# MCU_Core.net
KiCad netlist of a schematic drawn in Altium Designer
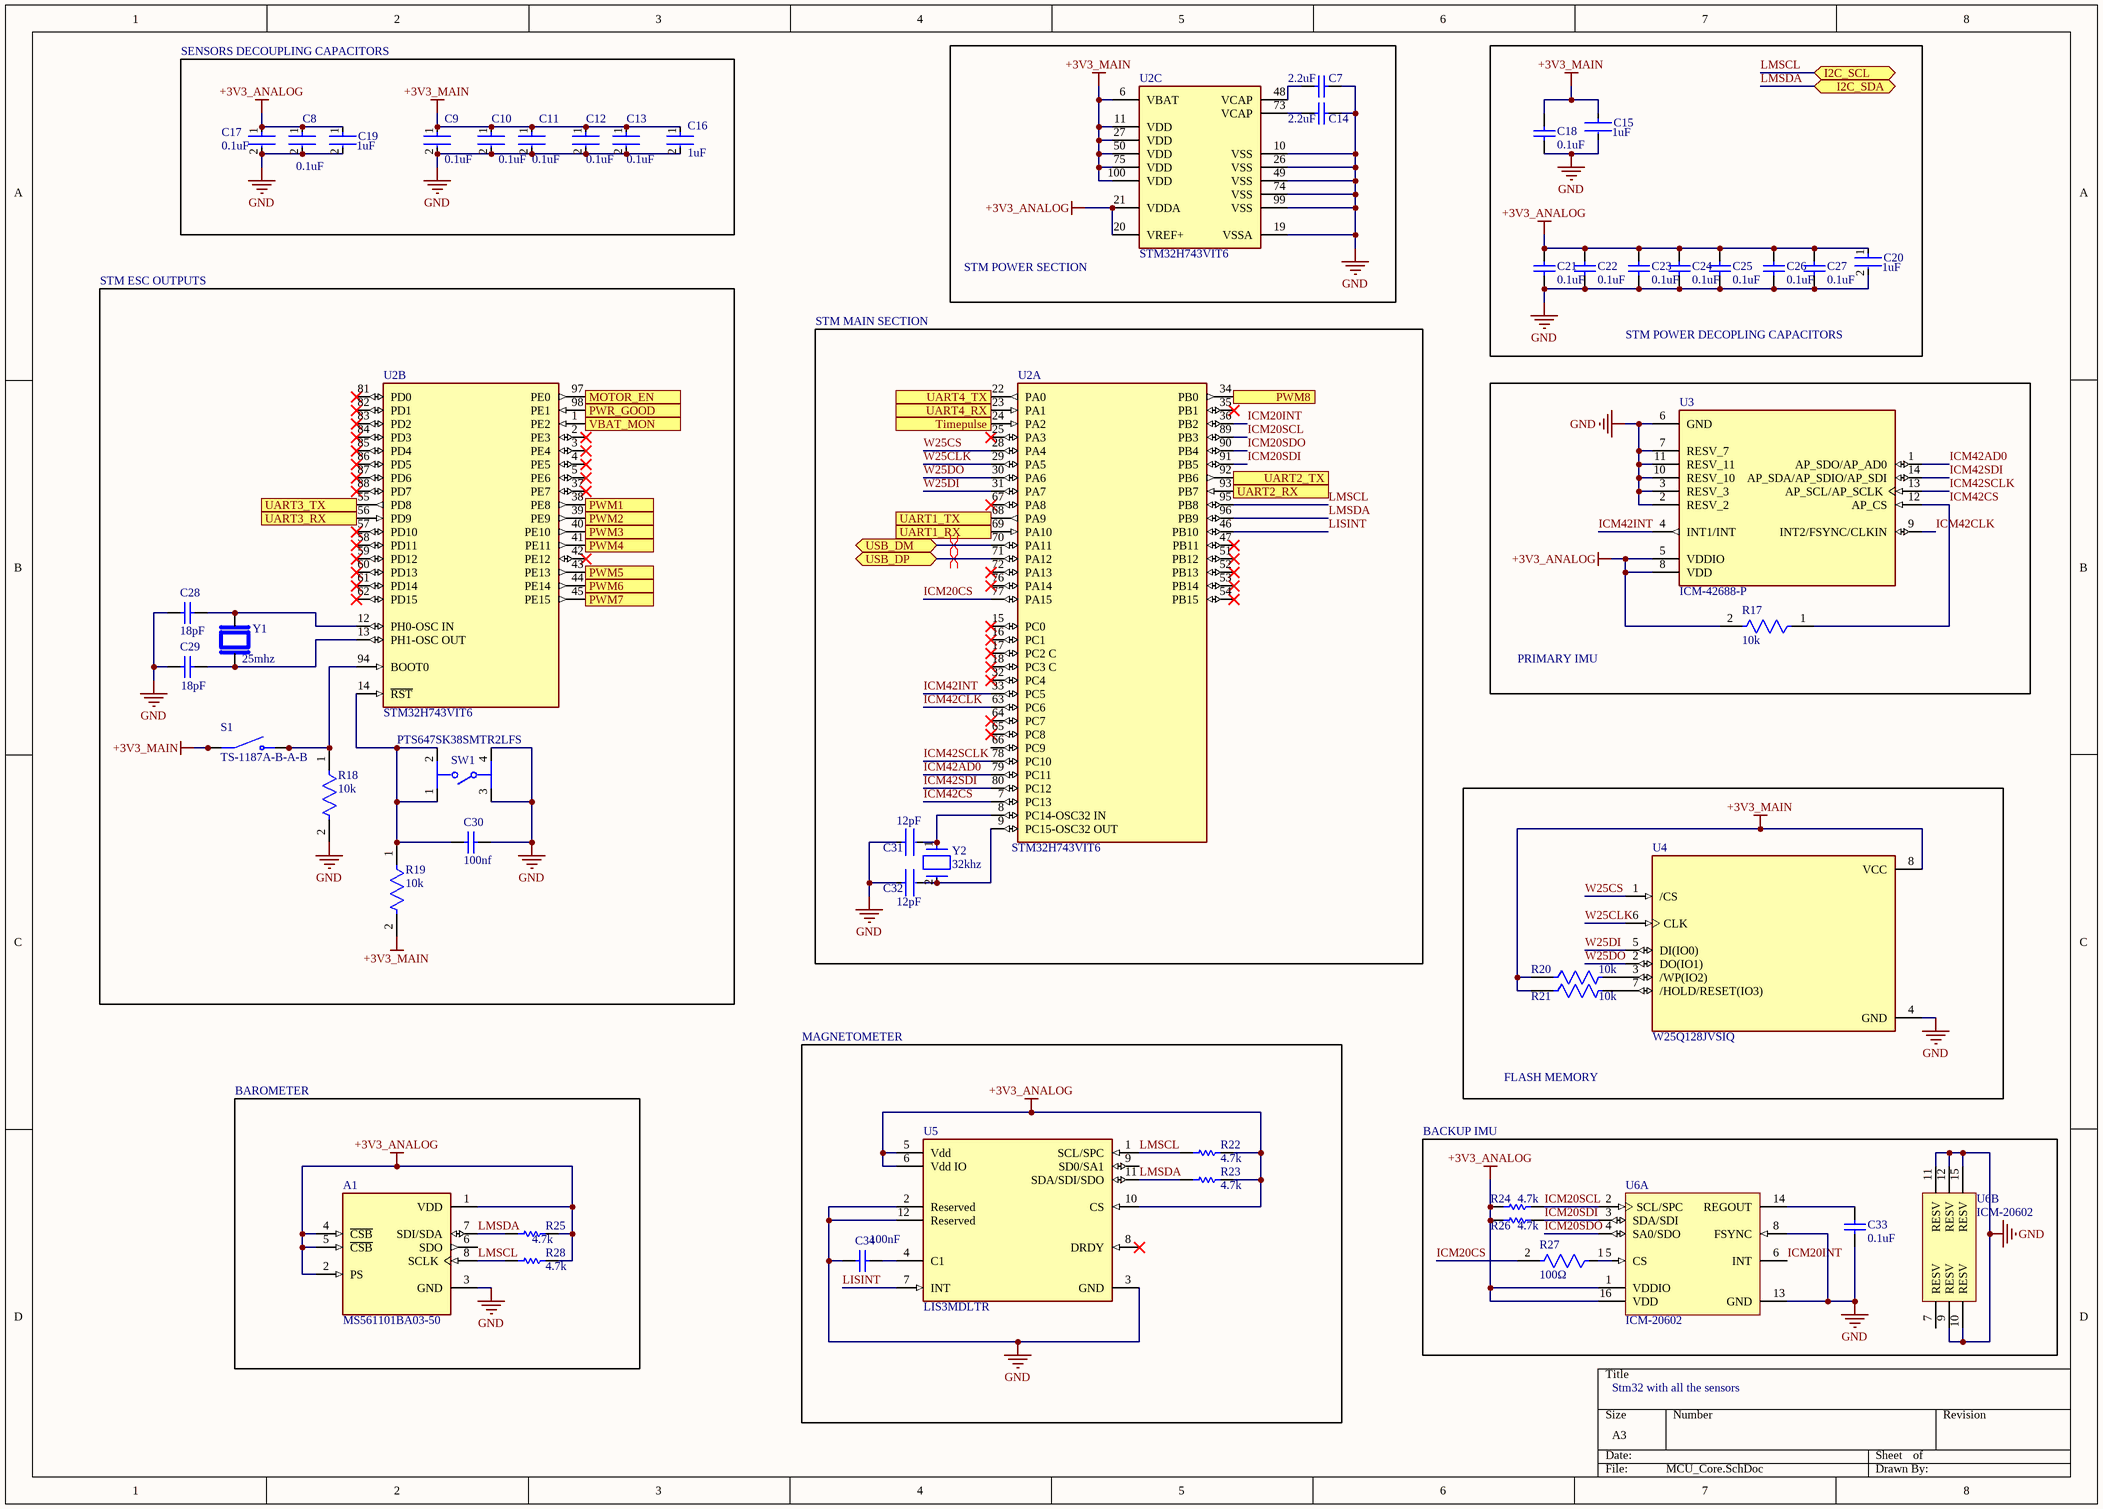
[diagram p0: MCU_Core.SchDoc]

(export (version "E")
  (design (tool "Eeschema 10.0.6"))
  (components
    (comp (ref "A1")
      (value "MS561101BA03-50")
      (footprint "XDCR_MS561101BA03-50")
      (description "Sensor;MS5611-BT M-CAPS 3X5X1MM T&R;Pressure;MS561101BA03-50 ¦ TE Connectivity MS561101BA03-50")
      (fields (field (name "MF") "TE Connectivity"))
      (libsource (lib "MS561101BA03-50") (part "MS561101BA03-50"))
    )
    (comp (ref "C7")
      (value "2.2uF")
      (footprint "CAPC1608X90X35ML15T15")
      (fields
        (field (name "PART NUMBER") "06031A2R2CAT2A")
        (field (name "MANUFACTURER") "AVX Interconnect / Elco")
      )
      (libsource (lib "Altium Content Vault") (part "CAP"))
    )
    (comp (ref "C8")
      (value "0.1uF")
      (footprint "FP-0201-L_0_6_0_05-W_0_3-MFG")
      (description "None")
      (fields (field (name "TOLERANCE") "10%"))
      (libsource (lib "Altium Content Vault") (part "b4654b650e69147ec39a6b967a45e02"))
    )
    (comp (ref "C9")
      (value "0.1uF")
      (footprint "FP-0201-L_0_6_0_05-W_0_3-MFG")
      (description "None")
      (fields (field (name "TOLERANCE") "10%"))
      (libsource (lib "Altium Content Vault") (part "b4654b650e69147ec39a6b967a45e02"))
    )
    (comp (ref "C10")
      (value "0.1uF")
      (footprint "FP-0201-L_0_6_0_05-W_0_3-MFG")
      (description "None")
      (fields (field (name "TOLERANCE") "10%"))
      (libsource (lib "Altium Content Vault") (part "b4654b650e69147ec39a6b967a45e02"))
    )
    (comp (ref "C11")
      (value "0.1uF")
      (footprint "FP-0201-L_0_6_0_05-W_0_3-MFG")
      (description "None")
      (fields (field (name "TOLERANCE") "10%"))
      (libsource (lib "Altium Content Vault") (part "b4654b650e69147ec39a6b967a45e02"))
    )
    (comp (ref "C12")
      (value "0.1uF")
      (footprint "FP-0201-L_0_6_0_05-W_0_3-MFG")
      (description "None")
      (fields (field (name "TOLERANCE") "10%"))
      (libsource (lib "Altium Content Vault") (part "b4654b650e69147ec39a6b967a45e02"))
    )
    (comp (ref "C13")
      (value "0.1uF")
      (footprint "FP-0201-L_0_6_0_05-W_0_3-MFG")
      (description "None")
      (fields (field (name "TOLERANCE") "10%"))
      (libsource (lib "Altium Content Vault") (part "b4654b650e69147ec39a6b967a45e02"))
    )
    (comp (ref "C14")
      (value "2.2uF")
      (footprint "CAPC1608X90X35ML15T15")
      (fields
        (field (name "PART NUMBER") "06031A2R2CAT2A")
        (field (name "MANUFACTURER") "AVX Interconnect / Elco")
      )
      (libsource (lib "Altium Content Vault") (part "CAP"))
    )
    (comp (ref "C15")
      (value "1uF")
      (footprint "FP-GCJ21B-0_3-IPC_B")
      (description "Multilayer Ceramic Capacitors MLCC - SMD/SMT 0805 1uF 10%, 16VDC,  X8L +15/-40%")
      (libsource (lib "") (part "02cd4be3c70576c341d710602a673aa_1"))
    )
    (comp (ref "C16")
      (value "1uF")
      (footprint "FP-GCJ21B-0_3-IPC_B")
      (description "Multilayer Ceramic Capacitors MLCC - SMD/SMT 0805 1uF 10%, 16VDC,  X8L +15/-40%")
      (libsource (lib "Altium Content Vault") (part "02cd4be3c70576c341d710602a673aa"))
    )
    (comp (ref "C17")
      (value "0.1uF")
      (footprint "FP-0201-L_0_6_0_05-W_0_3-MFG")
      (description "None")
      (fields (field (name "TOLERANCE") "10%"))
      (libsource (lib "Altium Content Vault") (part "b4654b650e69147ec39a6b967a45e02"))
    )
    (comp (ref "C18")
      (value "0.1uF")
      (footprint "CAPC1608X87X35ML15T15")
      (fields (field (name "PART NUMBER") "C0603T104K3RCLTU") (field (name "MANUFACTURER") "Kemet"))
      (libsource (lib "Altium Content Vault") (part "CAP"))
    )
    (comp (ref "C19")
      (value "1uF")
      (footprint "FP-GCJ21B-0_3-IPC_B")
      (description "Multilayer Ceramic Capacitors MLCC - SMD/SMT 0805 1uF 10%, 16VDC,  X8L +15/-40%")
      (libsource (lib "Altium Content Vault") (part "02cd4be3c70576c341d710602a673aa"))
    )
    (comp (ref "C20")
      (value "1uF")
      (footprint "FP-GCJ21B-0_3-IPC_B")
      (description "Multilayer Ceramic Capacitors MLCC - SMD/SMT 0805 1uF 10%, 16VDC,  X8L +15/-40%")
      (libsource (lib "Altium Content Vault") (part "02cd4be3c70576c341d710602a673aa"))
    )
    (comp (ref "C21")
      (value "0.1uF")
      (footprint "CAPC1608X87X35ML15T15")
      (fields (field (name "PART NUMBER") "C0603T104K3RCLTU") (field (name "MANUFACTURER") "Kemet"))
      (libsource (lib "Altium Content Vault") (part "CAP"))
    )
    (comp (ref "C22")
      (value "0.1uF")
      (footprint "CAPC1608X87X35ML15T15")
      (fields (field (name "PART NUMBER") "C0603T104K3RCLTU") (field (name "MANUFACTURER") "Kemet"))
      (libsource (lib "Altium Content Vault") (part "CAP"))
    )
    (comp (ref "C23")
      (value "0.1uF")
      (footprint "CAPC1608X87X35ML15T15")
      (fields (field (name "PART NUMBER") "C0603T104K3RCLTU") (field (name "MANUFACTURER") "Kemet"))
      (libsource (lib "Altium Content Vault") (part "CAP"))
    )
    (comp (ref "C24")
      (value "0.1uF")
      (footprint "CAPC1608X87X35ML15T15")
      (fields (field (name "PART NUMBER") "C0603T104K3RCLTU") (field (name "MANUFACTURER") "Kemet"))
      (libsource (lib "Altium Content Vault") (part "CAP"))
    )
    (comp (ref "C25")
      (value "0.1uF")
      (footprint "CAPC1608X87X35ML15T15")
      (fields (field (name "PART NUMBER") "C0603T104K3RCLTU") (field (name "MANUFACTURER") "Kemet"))
      (libsource (lib "Altium Content Vault") (part "CAP"))
    )
    (comp (ref "C26")
      (value "0.1uF")
      (footprint "CAPC1608X87X35ML15T15")
      (fields (field (name "PART NUMBER") "C0603T104K3RCLTU") (field (name "MANUFACTURER") "Kemet"))
      (libsource (lib "Altium Content Vault") (part "CAP"))
    )
    (comp (ref "C27")
      (value "0.1uF")
      (footprint "CAPC1608X87X35ML15T15")
      (fields (field (name "PART NUMBER") "C0603T104K3RCLTU") (field (name "MANUFACTURER") "Kemet"))
      (libsource (lib "Altium Content Vault") (part "CAP"))
    )
    (comp (ref "C28")
      (value "18pF")
      (footprint "CAPC1608X92X38NL15T08")
      (fields (field (name "PART NUMBER") "VJ0603A180JXAAC") (field (name "MANUFACTURER") "Vitramon"))
      (libsource (lib "Altium Content Vault") (part "CAP"))
    )
    (comp (ref "C29")
      (value "18pF")
      (footprint "CAPC1608X92X38NL15T08")
      (fields (field (name "PART NUMBER") "VJ0603A180JXAAC") (field (name "MANUFACTURER") "Vitramon"))
      (libsource (lib "Altium Content Vault") (part "CAP"))
    )
    (comp (ref "C30")
      (value "100nf")
      (footprint "CAPC1608X90X35LL15T15")
      (fields
        (field (name "MANUFACTURER") "AVX Interconnect / Elco")
        (field (name "PART NUMBER") "06035C104KAZ2A")
      )
      (libsource (lib "Altium Content Vault") (part "CAP"))
    )
    (comp (ref "C31")
      (value "12pF")
      (footprint "FP-C0603C-CF-MFG")
      (description "C0603 12 pF C0G 30ppm/°C 1.00% 100 V")
      (fields
        (field (name "MANUFACTURER") "KEMET")
        (field (name "OCTOPART") "https://octopart.com/c0603c120f1gacauto-kemet-91893820")
      )
      (libsource (lib "") (part "b4654b650e69147ec39a6b967a45e02_1"))
    )
    (comp (ref "C32")
      (value "12pF")
      (footprint "FP-C0603C-CF-MFG")
      (description "C0603 12 pF C0G 30ppm/°C 1.00% 100 V")
      (fields
        (field (name "MANUFACTURER") "KEMET")
        (field (name "OCTOPART") "https://octopart.com/c0603c120f1gacauto-kemet-91893820")
      )
      (libsource (lib "") (part "b4654b650e69147ec39a6b967a45e02_1"))
    )
    (comp (ref "C33")
      (value "0.1uF")
      (footprint "CAPC1608X87X35ML15T15")
      (fields (field (name "PART NUMBER") "C0603T104K3RCLTU") (field (name "MANUFACTURER") "Kemet"))
      (libsource (lib "Altium Content Vault") (part "CAP"))
    )
    (comp (ref "C34")
      (value "100nF")
      (footprint "CAPC1608X87X35ML15T15")
      (fields (field (name "PART NUMBER") "C0603T104K3RCLTU") (field (name "MANUFACTURER") "Kemet"))
      (libsource (lib "Altium Content Vault") (part "CAP"))
    )
    (comp (ref "R17")
      (value "10k")
      (footprint "FP-AC0603-IPC_A")
      (description "RES 10kΩ 5.00% 0.2W 0603")
      (libsource (lib "") (part "1029c3af85768c4190bb7ad29bc67b5_1"))
    )
    (comp (ref "R18")
      (value "10k")
      (footprint "FP-MCT0603-IPC_B")
      (description "RES SMD 100 OHM 1% 1/8W 0603")
      (libsource (lib "") (part "1029c3af85768c4190bb7ad29bc67b5_1"))
    )
    (comp (ref "R19")
      (value "10k")
      (footprint "FP-MCT0603-IPC_B")
      (description "RES SMD 100 OHM 1% 1/8W 0603")
      (libsource (lib "") (part "1029c3af85768c4190bb7ad29bc67b5_1"))
    )
    (comp (ref "R20")
      (value "10k")
      (footprint "FP-CRGP0805-IPC_C")
      (description "CRGP 0805 10K 1%")
      (fields (field (name "MANUFACTURER PART NUMBER") "CRGP0805F10K") (field (name "MANUFACTURER") "TE"))
      (libsource (lib "Altium Content Vault") (part "1029c3af85768c4190bb7ad29bc67b5"))
    )
    (comp (ref "R21")
      (value "10k")
      (footprint "FP-CRGP0805-IPC_C")
      (description "CRGP 0805 10K 1%")
      (fields (field (name "MANUFACTURER PART NUMBER") "CRGP0805F10K") (field (name "MANUFACTURER") "TE"))
      (libsource (lib "Altium Content Vault") (part "1029c3af85768c4190bb7ad29bc67b5"))
    )
    (comp (ref "R22")
      (value "4.7k")
      (footprint "RESC3225X75X50ML15T25")
      (fields (field (name "MANUFACTURER") "Vishay Dale") (field (name "PART NUMBER") "TNPW12104K70BETA"))
      (libsource (lib "Altium Content Vault") (part "RES"))
    )
    (comp (ref "R23")
      (value "4.7k")
      (footprint "RESC3225X75X50ML15T25")
      (fields (field (name "MANUFACTURER") "Vishay Dale") (field (name "PART NUMBER") "TNPW12104K70BETA"))
      (libsource (lib "Altium Content Vault") (part "RES"))
    )
    (comp (ref "R24")
      (value "4.7k")
      (footprint "RESC3225X75X50ML15T25")
      (fields (field (name "MANUFACTURER") "Vishay Dale") (field (name "PART NUMBER") "TNPW12104K70BETA"))
      (libsource (lib "Altium Content Vault") (part "RES"))
    )
    (comp (ref "R25")
      (value "4.7k")
      (footprint "RESC3225X75X50ML15T25")
      (fields (field (name "MANUFACTURER") "Vishay Dale") (field (name "PART NUMBER") "TNPW12104K70BETA"))
      (libsource (lib "Altium Content Vault") (part "RES"))
    )
    (comp (ref "R26")
      (value "4.7k")
      (footprint "RESC3225X75X50ML15T25")
      (fields (field (name "MANUFACTURER") "Vishay Dale") (field (name "PART NUMBER") "TNPW12104K70BETA"))
      (libsource (lib "Altium Content Vault") (part "RES"))
    )
    (comp (ref "R27")
      (value "100Ω")
      (footprint "FP-RMCF0805-IPC_A")
      (description "100Ω ±1% 0.125W 0805 Thick Film Chip Resistor AEC-Q200 compliant")
      (fields (field (name "TOLERANCE") "1%"))
      (libsource (lib "") (part "1029c3af85768c4190bb7ad29bc67b5_1"))
    )
    (comp (ref "R28")
      (value "4.7k")
      (footprint "RESC3225X75X50ML15T25")
      (fields (field (name "MANUFACTURER") "Vishay Dale") (field (name "PART NUMBER") "TNPW12104K70BETA"))
      (libsource (lib "Altium Content Vault") (part "RES"))
    )
    (comp (ref "S1")
      (value "TS-1187A-B-A-B")
      (footprint "SW_TS-1187A-B-A-B")
      (description "SPST 50mA @ 12VDC Top Actuated Round Button 160gf SMD Tactile Switches RoHS")
      (libsource (lib "TS-1187A-B-A-B") (part "TS-1187A-B-A-B"))
    )
    (comp (ref "SW1")
      (value "PTS647SK38SMTR2LFS")
      (footprint "FP-PTS647SK38SMTR2LFS-MFG")
      (description "TACT 4.5 X 4.5, 3.8 MM H, 2.5N,")
      (libsource (lib "Altium Content Vault") (part "1adf0dd01260c80cf25a44bfd6b99ba"))
    )
    (comp (ref "U2")
      (value "STM32H743VIT6")
      (footprint "FP-LQFP100-1L-MFG")
      (description "IC MCU 32BIT 2MB FLASH 100LQFP")
      (fields
        (field (name "OCTOPART") "https://octopart.com/stm32h743vit6-stmicroelectronics-76372527")
        (field (name "MANUFACTURER") "STMicroelectronics")
      )
      (libsource (lib "Altium Content Vault") (part "01082ce2885d1d16a22823c45526fe6"))
    )
    (comp (ref "U3")
      (value "ICM-42688-P")
      (footprint "PQFN50P300X250X97-14N")
      (description "Accelerometer, Gyroscope, 6 Axis Sensor Output")
      (libsource (lib "ICM-42688-P") (part "ICM-42688-P"))
    )
    (comp (ref "U4")
      (value "W25Q128JVSIQ")
      (footprint "SOIC127P790X216-8N")
      (description "FLASH - NOR Memory IC 128Mb (16M x 8) SPI - Quad I/O, QPI, DTR 133 MHz 8-SOIC")
      (fields (field (name "MF") "Winbond Electronics"))
      (libsource (lib "W25Q128JVSIQ") (part "W25Q128JVSIQ"))
    )
    (comp (ref "U5")
      (value "LIS3MDLTR")
      (footprint "FP-VFLGA-12-8365767-MFG")
      (description "SENSOR MR I2C/SPI 12LGA")
      (fields
        (field (name "OCTOPART") "https://octopart.com/lis3mdltr-stmicroelectronics-29403125")
        (field (name "MANUFACTURER") "STMicroelectronics")
      )
      (libsource (lib "Altium Content Vault") (part "41c0331d4207a07573b21020ef49d7d"))
    )
    (comp (ref "U6")
      (value "ICM-20602")
      (footprint "INSE-I62-16")
      (fields (field (name "MANUFACTURER") "InvenSense"))
      (libsource (lib "") (part "INSE-ICM-20602-16_1"))
    )
    (comp (ref "Y1")
      (value "25mhz")
      (footprint "XTAL_SXT32412BB07-25.000MT")
      (description "25 MHz Â±30ppm Crystal 12pF 50 Ohms 4-SMD, No Lead")
      (fields (field (name "MF") "Suntsu") (field (name "MP") "SXT32412BB07-25.000M"))
      (libsource (lib "SXT32412BB07-25.000MT") (part "SXT32412BB07-25.000MT"))
    )
    (comp (ref "Y2")
      (value "32khz")
      (footprint "FP-ABS07-MFG")
      (description "Crystal 32.768kHz ±20ppm (Tol) 12.5pF FUND 70kΩ 2-Pin CSMD T/R")
      (fields (field (name "TOLERANCE") "20ppm"))
      (libsource (lib "Altium Content Vault") (part "c23a69dc6c9e2f18f2079038eb95dd1"))
    )
  )
  (nets
    (net (code "1") (name "+3V3_ANALOG") (class "Default")
      (node (ref "A1") (pin "1") (pinfunction "VDD_1") (pintype "power_in"))
      (node (ref "A1") (pin "2") (pinfunction "PS_2") (pintype "input"))
      (node (ref "A1") (pin "4") (pinfunction "~{CSB}_4") (pintype "input"))
      (node (ref "A1") (pin "5") (pinfunction "~{CSB}_5") (pintype "input"))
      (node (ref "C17") (pin "1") (pinfunction "1_1") (pintype "passive"))
      (node (ref "C19") (pin "1") (pinfunction "1_1") (pintype "passive"))
      (node (ref "C20") (pin "1") (pinfunction "1_1") (pintype "passive"))
      (node (ref "C21") (pin "2") (pinfunction "2_2") (pintype "passive"))
      (node (ref "C22") (pin "2") (pinfunction "2_2") (pintype "passive"))
      (node (ref "C23") (pin "2") (pinfunction "2_2") (pintype "passive"))
      (node (ref "C24") (pin "2") (pinfunction "2_2") (pintype "passive"))
      (node (ref "C25") (pin "2") (pinfunction "2_2") (pintype "passive"))
      (node (ref "C26") (pin "2") (pinfunction "2_2") (pintype "passive"))
      (node (ref "C27") (pin "2") (pinfunction "2_2") (pintype "passive"))
      (node (ref "C8") (pin "1") (pinfunction "1_1") (pintype "passive"))
      (node (ref "R17") (pin "2") (pinfunction "2_2") (pintype "passive"))
      (node (ref "R22") (pin "2") (pinfunction "2_2") (pintype "passive"))
      (node (ref "R23") (pin "2") (pinfunction "2_2") (pintype "passive"))
      (node (ref "R24") (pin "2") (pinfunction "2_2") (pintype "passive"))
      (node (ref "R25") (pin "2") (pinfunction "2_2") (pintype "passive"))
      (node (ref "R26") (pin "2") (pinfunction "2_2") (pintype "passive"))
      (node (ref "R28") (pin "2") (pinfunction "2_2") (pintype "passive"))
      (node (ref "U2") (pin "20") (pinfunction "VREF+_20") (pintype "power_in"))
      (node (ref "U2") (pin "21") (pinfunction "VDDA_21") (pintype "power_in"))
      (node (ref "U3") (pin "5") (pinfunction "VDDIO_5") (pintype "power_in"))
      (node (ref "U3") (pin "8") (pinfunction "VDD_8") (pintype "power_in"))
      (node (ref "U5") (pin "10") (pinfunction "CS_10") (pintype "input"))
      (node (ref "U5") (pin "5") (pinfunction "Vdd_5") (pintype "power_in"))
      (node (ref "U5") (pin "6") (pinfunction "Vdd_IO_6") (pintype "power_in"))
      (node (ref "U6") (pin "1") (pinfunction "VDDIO_1") (pintype "power_in"))
      (node (ref "U6") (pin "16") (pinfunction "VDD_16") (pintype "power_in"))
    )
    (net (code "2") (name "+3V3_MAIN") (class "Default")
      (node (ref "C10") (pin "1") (pinfunction "1_1") (pintype "passive"))
      (node (ref "C11") (pin "1") (pinfunction "1_1") (pintype "passive"))
      (node (ref "C12") (pin "1") (pinfunction "1_1") (pintype "passive"))
      (node (ref "C13") (pin "1") (pinfunction "1_1") (pintype "passive"))
      (node (ref "C15") (pin "1") (pinfunction "1_1") (pintype "passive"))
      (node (ref "C16") (pin "1") (pinfunction "1_1") (pintype "passive"))
      (node (ref "C18") (pin "2") (pinfunction "2_2") (pintype "passive"))
      (node (ref "C9") (pin "1") (pinfunction "1_1") (pintype "passive"))
      (node (ref "R19") (pin "2") (pinfunction "2_2") (pintype "passive"))
      (node (ref "R20") (pin "1") (pinfunction "1_1") (pintype "passive"))
      (node (ref "R21") (pin "1") (pinfunction "1_1") (pintype "passive"))
      (node (ref "S1") (pin "A") (pinfunction "COM_A") (pintype "passive"))
      (node (ref "S1") (pin "B") (pinfunction "COM_B") (pintype "passive"))
      (node (ref "U2") (pin "100") (pinfunction "VDD_100") (pintype "power_in"))
      (node (ref "U2") (pin "11") (pinfunction "VDD_11") (pintype "power_in"))
      (node (ref "U2") (pin "27") (pinfunction "VDD_27") (pintype "power_in"))
      (node (ref "U2") (pin "50") (pinfunction "VDD_50") (pintype "power_in"))
      (node (ref "U2") (pin "6") (pinfunction "VBAT_6") (pintype "power_in"))
      (node (ref "U2") (pin "75") (pinfunction "VDD_75") (pintype "power_in"))
      (node (ref "U4") (pin "8") (pinfunction "VCC_8") (pintype "power_in"))
    )
    (net (code "3") (name "/ICM20CS") (class "Default")
      (node (ref "R27") (pin "2") (pinfunction "2_2") (pintype "passive"))
      (node (ref "U2") (pin "77") (pinfunction "PA15_77") (pintype "bidirectional"))
    )
    (net (code "4") (name "/ICM20INT") (class "Default")
      (node (ref "U2") (pin "36") (pinfunction "PB2_36") (pintype "bidirectional"))
      (node (ref "U6") (pin "6") (pinfunction "INT_6") (pintype "open_collector"))
    )
    (net (code "5") (name "/ICM20SCL") (class "Default")
      (node (ref "R24") (pin "1") (pinfunction "1_1") (pintype "passive"))
      (node (ref "U2") (pin "89") (pinfunction "PB3_89") (pintype "bidirectional"))
      (node (ref "U6") (pin "2") (pinfunction "SCL/SPC_2") (pintype "input"))
    )
    (net (code "6") (name "/ICM20SDI") (class "Default")
      (node (ref "R26") (pin "1") (pinfunction "1_1") (pintype "passive"))
      (node (ref "U2") (pin "91") (pinfunction "PB5_91") (pintype "bidirectional"))
      (node (ref "U6") (pin "3") (pinfunction "SDA/SDI_3") (pintype "bidirectional"))
    )
    (net (code "7") (name "/ICM20SDO") (class "Default")
      (node (ref "U2") (pin "90") (pinfunction "PB4_90") (pintype "bidirectional"))
      (node (ref "U6") (pin "4") (pinfunction "SA0/SDO_4") (pintype "bidirectional"))
    )
    (net (code "8") (name "/ICM42AD0") (class "Default")
      (node (ref "U2") (pin "79") (pinfunction "PC11_79") (pintype "bidirectional"))
      (node (ref "U3") (pin "1") (pinfunction "AP_SDO/AP_AD0_1") (pintype "bidirectional"))
    )
    (net (code "9") (name "/ICM42CLK") (class "Default")
      (node (ref "U2") (pin "63") (pinfunction "PC6_63") (pintype "bidirectional"))
      (node (ref "U3") (pin "9") (pinfunction "INT2/FSYNC/CLKIN_9") (pintype "bidirectional"))
    )
    (net (code "10") (name "/ICM42CS") (class "Default")
      (node (ref "R17") (pin "1") (pinfunction "1_1") (pintype "passive"))
      (node (ref "U2") (pin "7") (pinfunction "PC13_7") (pintype "bidirectional"))
      (node (ref "U3") (pin "12") (pinfunction "AP_CS_12") (pintype "input"))
    )
    (net (code "11") (name "/ICM42INT") (class "Default")
      (node (ref "U2") (pin "33") (pinfunction "PC5_33") (pintype "bidirectional"))
      (node (ref "U3") (pin "4") (pinfunction "INT1/INT_4") (pintype "output"))
    )
    (net (code "12") (name "/ICM42SCLK") (class "Default")
      (node (ref "U2") (pin "78") (pinfunction "PC10_78") (pintype "bidirectional"))
      (node (ref "U3") (pin "13") (pinfunction "AP_SCL/AP_SCLK_13") (pintype "input"))
    )
    (net (code "13") (name "/ICM42SDI") (class "Default")
      (node (ref "U2") (pin "80") (pinfunction "PC12_80") (pintype "bidirectional"))
      (node (ref "U3") (pin "14") (pinfunction "AP_SDA/AP_SDIO/AP_SDI_14") (pintype "bidirectional"))
    )
    (net (code "14") (name "/LISINT") (class "Default")
      (node (ref "U2") (pin "46") (pinfunction "PB10_46") (pintype "bidirectional"))
      (node (ref "U5") (pin "7") (pinfunction "INT_7") (pintype "input"))
    )
    (net (code "15") (name "/LMSCL") (class "Default")
      (node (ref "A1") (pin "8") (pinfunction "SCLK_8") (pintype "input"))
      (node (ref "R22") (pin "1") (pinfunction "1_1") (pintype "passive"))
      (node (ref "R28") (pin "1") (pinfunction "1_1") (pintype "passive"))
      (node (ref "U2") (pin "95") (pinfunction "PB8_95") (pintype "bidirectional"))
      (node (ref "U5") (pin "1") (pinfunction "SCL/SPC_1") (pintype "input"))
    )
    (net (code "16") (name "/LMSDA") (class "Default")
      (node (ref "A1") (pin "7") (pinfunction "SDI/SDA_7") (pintype "bidirectional"))
      (node (ref "R23") (pin "1") (pinfunction "1_1") (pintype "passive"))
      (node (ref "R25") (pin "1") (pinfunction "1_1") (pintype "passive"))
      (node (ref "U2") (pin "96") (pinfunction "PB9_96") (pintype "bidirectional"))
      (node (ref "U5") (pin "11") (pinfunction "SDA/SDI/SDO_11") (pintype "bidirectional"))
    )
    (net (code "17") (name "/MOTOR_EN") (class "Default")
      (node (ref "U2") (pin "97") (pinfunction "PE0_97") (pintype "bidirectional"))
    )
    (net (code "18") (name "/PWM1") (class "Default")
      (node (ref "U2") (pin "38") (pinfunction "PE8_38") (pintype "bidirectional"))
    )
    (net (code "19") (name "/PWM2") (class "Default")
      (node (ref "U2") (pin "39") (pinfunction "PE9_39") (pintype "bidirectional"))
    )
    (net (code "20") (name "/PWM3") (class "Default")
      (node (ref "U2") (pin "40") (pinfunction "PE10_40") (pintype "bidirectional"))
    )
    (net (code "21") (name "/PWM4") (class "Default")
      (node (ref "U2") (pin "41") (pinfunction "PE11_41") (pintype "bidirectional"))
    )
    (net (code "22") (name "/PWM5") (class "Default")
      (node (ref "U2") (pin "43") (pinfunction "PE13_43") (pintype "bidirectional"))
    )
    (net (code "23") (name "/PWM6") (class "Default")
      (node (ref "U2") (pin "44") (pinfunction "PE14_44") (pintype "bidirectional"))
    )
    (net (code "24") (name "/PWM7") (class "Default")
      (node (ref "U2") (pin "45") (pinfunction "PE15_45") (pintype "bidirectional"))
    )
    (net (code "25") (name "/PWM8") (class "Default")
      (node (ref "U2") (pin "34") (pinfunction "PB0_34") (pintype "output"))
    )
    (net (code "26") (name "/PWR_GOOD") (class "Default")
      (node (ref "U2") (pin "98") (pinfunction "PE1_98") (pintype "bidirectional"))
    )
    (net (code "27") (name "/Timepulse") (class "Default")
      (node (ref "U2") (pin "24") (pinfunction "PA2_24") (pintype "input"))
    )
    (net (code "28") (name "/UART1_RX") (class "Default")
      (node (ref "U2") (pin "69") (pinfunction "PA10_69") (pintype "input"))
    )
    (net (code "29") (name "/UART1_TX") (class "Default")
      (node (ref "U2") (pin "68") (pinfunction "PA9_68") (pintype "output"))
    )
    (net (code "30") (name "/UART2_RX") (class "Default")
      (node (ref "U2") (pin "93") (pinfunction "PB7_93") (pintype "input"))
    )
    (net (code "31") (name "/UART2_TX") (class "Default")
      (node (ref "U2") (pin "92") (pinfunction "PB6_92") (pintype "output"))
    )
    (net (code "32") (name "/UART3_RX") (class "Default")
      (node (ref "U2") (pin "56") (pinfunction "PD9_56") (pintype "bidirectional"))
    )
    (net (code "33") (name "/UART3_TX") (class "Default")
      (node (ref "U2") (pin "55") (pinfunction "PD8_55") (pintype "bidirectional"))
    )
    (net (code "34") (name "/UART4_RX") (class "Default")
      (node (ref "U2") (pin "23") (pinfunction "PA1_23") (pintype "input"))
    )
    (net (code "35") (name "/UART4_TX") (class "Default")
      (node (ref "U2") (pin "22") (pinfunction "PA0_22") (pintype "output"))
    )
    (net (code "36") (name "/USB_DM") (class "Default")
      (node (ref "U2") (pin "70") (pinfunction "PA11_70") (pintype "bidirectional"))
    )
    (net (code "37") (name "/USB_DP") (class "Default")
      (node (ref "U2") (pin "71") (pinfunction "PA12_71") (pintype "bidirectional"))
    )
    (net (code "38") (name "/VBAT_MON") (class "Default")
      (node (ref "U2") (pin "1") (pinfunction "PE2_1") (pintype "bidirectional"))
    )
    (net (code "39") (name "/W25CLK") (class "Default")
      (node (ref "U2") (pin "29") (pinfunction "PA5_29") (pintype "bidirectional"))
      (node (ref "U4") (pin "6") (pinfunction "CLK_6") (pintype "input"))
    )
    (net (code "40") (name "/W25CS") (class "Default")
      (node (ref "U2") (pin "28") (pinfunction "PA4_28") (pintype "bidirectional"))
      (node (ref "U4") (pin "1") (pinfunction "/CS_1") (pintype "input"))
    )
    (net (code "41") (name "/W25DI") (class "Default")
      (node (ref "U2") (pin "31") (pinfunction "PA7_31") (pintype "bidirectional"))
      (node (ref "U4") (pin "5") (pinfunction "DI(IO0)_5") (pintype "bidirectional"))
    )
    (net (code "42") (name "/W25DO") (class "Default")
      (node (ref "U2") (pin "30") (pinfunction "PA6_30") (pintype "bidirectional"))
      (node (ref "U4") (pin "2") (pinfunction "DO(IO1)_2") (pintype "bidirectional"))
    )
    (net (code "43") (name "GND") (class "Default")
      (node (ref "A1") (pin "3") (pinfunction "GND_3") (pintype "power_in"))
      (node (ref "C10") (pin "2") (pinfunction "2_2") (pintype "passive"))
      (node (ref "C11") (pin "2") (pinfunction "2_2") (pintype "passive"))
      (node (ref "C12") (pin "2") (pinfunction "2_2") (pintype "passive"))
      (node (ref "C13") (pin "2") (pinfunction "2_2") (pintype "passive"))
      (node (ref "C14") (pin "2") (pinfunction "2_2") (pintype "passive"))
      (node (ref "C15") (pin "2") (pinfunction "2_2") (pintype "passive"))
      (node (ref "C16") (pin "2") (pinfunction "2_2") (pintype "passive"))
      (node (ref "C17") (pin "2") (pinfunction "2_2") (pintype "passive"))
      (node (ref "C18") (pin "1") (pinfunction "1_1") (pintype "passive"))
      (node (ref "C19") (pin "2") (pinfunction "2_2") (pintype "passive"))
      (node (ref "C20") (pin "2") (pinfunction "2_2") (pintype "passive"))
      (node (ref "C21") (pin "1") (pinfunction "1_1") (pintype "passive"))
      (node (ref "C22") (pin "1") (pinfunction "1_1") (pintype "passive"))
      (node (ref "C23") (pin "1") (pinfunction "1_1") (pintype "passive"))
      (node (ref "C24") (pin "1") (pinfunction "1_1") (pintype "passive"))
      (node (ref "C25") (pin "1") (pinfunction "1_1") (pintype "passive"))
      (node (ref "C26") (pin "1") (pinfunction "1_1") (pintype "passive"))
      (node (ref "C27") (pin "1") (pinfunction "1_1") (pintype "passive"))
      (node (ref "C28") (pin "1") (pinfunction "1_1") (pintype "passive"))
      (node (ref "C29") (pin "1") (pinfunction "1_1") (pintype "passive"))
      (node (ref "C30") (pin "1") (pinfunction "1_1") (pintype "passive"))
      (node (ref "C31") (pin "1") (pinfunction "1_1") (pintype "passive"))
      (node (ref "C32") (pin "1") (pinfunction "1_1") (pintype "passive"))
      (node (ref "C33") (pin "1") (pinfunction "1_1") (pintype "passive"))
      (node (ref "C34") (pin "1") (pinfunction "1_1") (pintype "passive"))
      (node (ref "C7") (pin "2") (pinfunction "2_2") (pintype "passive"))
      (node (ref "C8") (pin "2") (pinfunction "2_2") (pintype "passive"))
      (node (ref "C9") (pin "2") (pinfunction "2_2") (pintype "passive"))
      (node (ref "R18") (pin "2") (pinfunction "2_2") (pintype "passive"))
      (node (ref "SW1") (pin "3") (pinfunction "3_3") (pintype "passive"))
      (node (ref "SW1") (pin "4") (pinfunction "4_4") (pintype "passive"))
      (node (ref "U2") (pin "10") (pinfunction "VSS_10") (pintype "power_in"))
      (node (ref "U2") (pin "19") (pinfunction "VSSA_19") (pintype "power_in"))
      (node (ref "U2") (pin "26") (pinfunction "VSS_26") (pintype "power_in"))
      (node (ref "U2") (pin "49") (pinfunction "VSS_49") (pintype "power_in"))
      (node (ref "U2") (pin "74") (pinfunction "VSS_74") (pintype "power_in"))
      (node (ref "U2") (pin "99") (pinfunction "VSS_99") (pintype "power_in"))
      (node (ref "U3") (pin "10") (pinfunction "RESV_10_10") (pintype "passive"))
      (node (ref "U3") (pin "11") (pinfunction "RESV_11_11") (pintype "passive"))
      (node (ref "U3") (pin "2") (pinfunction "RESV_2_2") (pintype "passive"))
      (node (ref "U3") (pin "3") (pinfunction "RESV_3_3") (pintype "passive"))
      (node (ref "U3") (pin "6") (pinfunction "GND_6") (pintype "power_in"))
      (node (ref "U3") (pin "7") (pinfunction "RESV_7_7") (pintype "passive"))
      (node (ref "U4") (pin "4") (pinfunction "GND_4") (pintype "power_in"))
      (node (ref "U5") (pin "12") (pinfunction "Reserved_12") (pintype "passive"))
      (node (ref "U5") (pin "2") (pinfunction "Reserved_2") (pintype "passive"))
      (node (ref "U5") (pin "3") (pinfunction "GND_3") (pintype "power_in"))
      (node (ref "U6") (pin "10") (pinfunction "RESV_10") (pintype "passive"))
      (node (ref "U6") (pin "11") (pinfunction "RESV_11") (pintype "passive"))
      (node (ref "U6") (pin "12") (pinfunction "RESV_12") (pintype "passive"))
      (node (ref "U6") (pin "13") (pinfunction "GND_13") (pintype "power_in"))
      (node (ref "U6") (pin "15") (pinfunction "RESV_15") (pintype "passive"))
      (node (ref "U6") (pin "8") (pinfunction "FSYNC_8") (pintype "input"))
      (node (ref "U6") (pin "9") (pinfunction "RESV_9") (pintype "passive"))
    )
    (net (code "44") (name "Net-(C7-Pad1)") (class "Default")
      (node (ref "C7") (pin "1") (pinfunction "1_1") (pintype "passive"))
      (node (ref "U2") (pin "48") (pinfunction "VCAP_48") (pintype "passive"))
    )
    (net (code "45") (name "Net-(C14-Pad1)") (class "Default")
      (node (ref "C14") (pin "1") (pinfunction "1_1") (pintype "passive"))
      (node (ref "U2") (pin "73") (pinfunction "VCAP_73") (pintype "passive"))
    )
    (net (code "46") (name "Net-(U2A-PC14-OSC32_IN)") (class "Default")
      (node (ref "C31") (pin "2") (pinfunction "2_2") (pintype "passive"))
      (node (ref "U2") (pin "8") (pinfunction "PC14-OSC32_IN_8") (pintype "bidirectional"))
      (node (ref "Y2") (pin "1") (pinfunction "1_1") (pintype "passive"))
    )
    (net (code "47") (name "Net-(U2A-PC15-OSC32_OUT)") (class "Default")
      (node (ref "C32") (pin "2") (pinfunction "2_2") (pintype "passive"))
      (node (ref "U2") (pin "9") (pinfunction "PC15-OSC32_OUT_9") (pintype "bidirectional"))
      (node (ref "Y2") (pin "2") (pinfunction "2_2") (pintype "passive"))
    )
    (net (code "48") (name "Net-(U2B-BOOT0)") (class "Default")
      (node (ref "R18") (pin "1") (pinfunction "1_1") (pintype "passive"))
      (node (ref "S1") (pin "C") (pinfunction "NO_C") (pintype "passive"))
      (node (ref "S1") (pin "D") (pinfunction "NO_D") (pintype "passive"))
      (node (ref "U2") (pin "94") (pinfunction "BOOT0_94") (pintype "input"))
    )
    (net (code "49") (name "Net-(U2B-PH0-OSC_IN)") (class "Default")
      (node (ref "C28") (pin "2") (pinfunction "2_2") (pintype "passive"))
      (node (ref "U2") (pin "12") (pinfunction "PH0-OSC_IN_12") (pintype "bidirectional"))
      (node (ref "Y1") (pin "3") (pinfunction "3_3") (pintype "passive"))
    )
    (net (code "50") (name "Net-(U2B-PH1-OSC_OUT)") (class "Default")
      (node (ref "C29") (pin "2") (pinfunction "2_2") (pintype "passive"))
      (node (ref "U2") (pin "13") (pinfunction "PH1-OSC_OUT_13") (pintype "bidirectional"))
      (node (ref "Y1") (pin "1") (pinfunction "1_1") (pintype "passive"))
    )
    (net (code "51") (name "Net-(U2B-~{RST})") (class "Default")
      (node (ref "C30") (pin "2") (pinfunction "2_2") (pintype "passive"))
      (node (ref "R19") (pin "1") (pinfunction "1_1") (pintype "passive"))
      (node (ref "SW1") (pin "1") (pinfunction "1_1") (pintype "passive"))
      (node (ref "SW1") (pin "2") (pinfunction "2_2") (pintype "passive"))
      (node (ref "U2") (pin "14") (pinfunction "~{RST}_14") (pintype "input"))
    )
    (net (code "52") (name "Net-(U4-{slash}HOLD{slash}RESET(IO3))") (class "Default")
      (node (ref "R21") (pin "2") (pinfunction "2_2") (pintype "passive"))
      (node (ref "U4") (pin "7") (pinfunction "/HOLD/RESET(IO3)_7") (pintype "bidirectional"))
    )
    (net (code "53") (name "Net-(U4-{slash}WP(IO2))") (class "Default")
      (node (ref "R20") (pin "2") (pinfunction "2_2") (pintype "passive"))
      (node (ref "U4") (pin "3") (pinfunction "/WP(IO2)_3") (pintype "bidirectional"))
    )
    (net (code "54") (name "Net-(U5-C1)") (class "Default")
      (node (ref "C34") (pin "2") (pinfunction "2_2") (pintype "passive"))
      (node (ref "U5") (pin "4") (pinfunction "C1_4") (pintype "passive"))
    )
    (net (code "55") (name "Net-(U6A-CS)") (class "Default")
      (node (ref "R27") (pin "1") (pinfunction "1_1") (pintype "passive"))
      (node (ref "U6") (pin "5") (pinfunction "CS_5") (pintype "input"))
    )
    (net (code "56") (name "Net-(U6A-REGOUT)") (class "Default")
      (node (ref "C33") (pin "2") (pinfunction "2_2") (pintype "passive"))
      (node (ref "U6") (pin "14") (pinfunction "REGOUT_14") (pintype "passive"))
    )
    (net (code "57") (name "unconnected-(A1-SDO-Pad6)") (class "Default")
      (node (ref "A1") (pin "6") (pinfunction "SDO_6") (pintype "output"))
    )
    (net (code "58") (name "unconnected-(U2A-PA3-Pad25)") (class "Default")
      (node (ref "U2") (pin "25") (pinfunction "PA3_25") (pintype "bidirectional+no_connect"))
    )
    (net (code "59") (name "unconnected-(U2A-PA8-Pad67)") (class "Default")
      (node (ref "U2") (pin "67") (pinfunction "PA8_67") (pintype "bidirectional+no_connect"))
    )
    (net (code "60") (name "unconnected-(U2A-PA13-Pad72)") (class "Default")
      (node (ref "U2") (pin "72") (pinfunction "PA13_72") (pintype "bidirectional+no_connect"))
    )
    (net (code "61") (name "unconnected-(U2A-PA14-Pad76)") (class "Default")
      (node (ref "U2") (pin "76") (pinfunction "PA14_76") (pintype "bidirectional+no_connect"))
    )
    (net (code "62") (name "unconnected-(U2A-PB1-Pad35)") (class "Default")
      (node (ref "U2") (pin "35") (pinfunction "PB1_35") (pintype "bidirectional+no_connect"))
    )
    (net (code "63") (name "unconnected-(U2A-PB11-Pad47)") (class "Default")
      (node (ref "U2") (pin "47") (pinfunction "PB11_47") (pintype "bidirectional+no_connect"))
    )
    (net (code "64") (name "unconnected-(U2A-PB12-Pad51)") (class "Default")
      (node (ref "U2") (pin "51") (pinfunction "PB12_51") (pintype "bidirectional+no_connect"))
    )
    (net (code "65") (name "unconnected-(U2A-PB13-Pad52)") (class "Default")
      (node (ref "U2") (pin "52") (pinfunction "PB13_52") (pintype "bidirectional+no_connect"))
    )
    (net (code "66") (name "unconnected-(U2A-PB14-Pad53)") (class "Default")
      (node (ref "U2") (pin "53") (pinfunction "PB14_53") (pintype "bidirectional+no_connect"))
    )
    (net (code "67") (name "unconnected-(U2A-PB15-Pad54)") (class "Default")
      (node (ref "U2") (pin "54") (pinfunction "PB15_54") (pintype "bidirectional+no_connect"))
    )
    (net (code "68") (name "unconnected-(U2A-PC0-Pad15)") (class "Default")
      (node (ref "U2") (pin "15") (pinfunction "PC0_15") (pintype "bidirectional+no_connect"))
    )
    (net (code "69") (name "unconnected-(U2A-PC1-Pad16)") (class "Default")
      (node (ref "U2") (pin "16") (pinfunction "PC1_16") (pintype "bidirectional+no_connect"))
    )
    (net (code "70") (name "unconnected-(U2A-PC2_C-Pad17)") (class "Default")
      (node (ref "U2") (pin "17") (pinfunction "PC2_C_17") (pintype "bidirectional+no_connect"))
    )
    (net (code "71") (name "unconnected-(U2A-PC3_C-Pad18)") (class "Default")
      (node (ref "U2") (pin "18") (pinfunction "PC3_C_18") (pintype "bidirectional+no_connect"))
    )
    (net (code "72") (name "unconnected-(U2A-PC4-Pad32)") (class "Default")
      (node (ref "U2") (pin "32") (pinfunction "PC4_32") (pintype "bidirectional+no_connect"))
    )
    (net (code "73") (name "unconnected-(U2A-PC7-Pad64)") (class "Default")
      (node (ref "U2") (pin "64") (pinfunction "PC7_64") (pintype "bidirectional+no_connect"))
    )
    (net (code "74") (name "unconnected-(U2A-PC8-Pad65)") (class "Default")
      (node (ref "U2") (pin "65") (pinfunction "PC8_65") (pintype "bidirectional+no_connect"))
    )
    (net (code "75") (name "unconnected-(U2A-PC9-Pad66)") (class "Default")
      (node (ref "U2") (pin "66") (pinfunction "PC9_66") (pintype "bidirectional"))
    )
    (net (code "76") (name "unconnected-(U2B-PD0-Pad81)") (class "Default")
      (node (ref "U2") (pin "81") (pinfunction "PD0_81") (pintype "bidirectional+no_connect"))
    )
    (net (code "77") (name "unconnected-(U2B-PD1-Pad82)") (class "Default")
      (node (ref "U2") (pin "82") (pinfunction "PD1_82") (pintype "bidirectional+no_connect"))
    )
    (net (code "78") (name "unconnected-(U2B-PD2-Pad83)") (class "Default")
      (node (ref "U2") (pin "83") (pinfunction "PD2_83") (pintype "bidirectional+no_connect"))
    )
    (net (code "79") (name "unconnected-(U2B-PD3-Pad84)") (class "Default")
      (node (ref "U2") (pin "84") (pinfunction "PD3_84") (pintype "bidirectional+no_connect"))
    )
    (net (code "80") (name "unconnected-(U2B-PD4-Pad85)") (class "Default")
      (node (ref "U2") (pin "85") (pinfunction "PD4_85") (pintype "bidirectional+no_connect"))
    )
    (net (code "81") (name "unconnected-(U2B-PD5-Pad86)") (class "Default")
      (node (ref "U2") (pin "86") (pinfunction "PD5_86") (pintype "bidirectional+no_connect"))
    )
    (net (code "82") (name "unconnected-(U2B-PD6-Pad87)") (class "Default")
      (node (ref "U2") (pin "87") (pinfunction "PD6_87") (pintype "bidirectional+no_connect"))
    )
    (net (code "83") (name "unconnected-(U2B-PD7-Pad88)") (class "Default")
      (node (ref "U2") (pin "88") (pinfunction "PD7_88") (pintype "bidirectional+no_connect"))
    )
    (net (code "84") (name "unconnected-(U2B-PD10-Pad57)") (class "Default")
      (node (ref "U2") (pin "57") (pinfunction "PD10_57") (pintype "bidirectional+no_connect"))
    )
    (net (code "85") (name "unconnected-(U2B-PD11-Pad58)") (class "Default")
      (node (ref "U2") (pin "58") (pinfunction "PD11_58") (pintype "bidirectional+no_connect"))
    )
    (net (code "86") (name "unconnected-(U2B-PD12-Pad59)") (class "Default")
      (node (ref "U2") (pin "59") (pinfunction "PD12_59") (pintype "bidirectional+no_connect"))
    )
    (net (code "87") (name "unconnected-(U2B-PD13-Pad60)") (class "Default")
      (node (ref "U2") (pin "60") (pinfunction "PD13_60") (pintype "bidirectional+no_connect"))
    )
    (net (code "88") (name "unconnected-(U2B-PD14-Pad61)") (class "Default")
      (node (ref "U2") (pin "61") (pinfunction "PD14_61") (pintype "bidirectional+no_connect"))
    )
    (net (code "89") (name "unconnected-(U2B-PD15-Pad62)") (class "Default")
      (node (ref "U2") (pin "62") (pinfunction "PD15_62") (pintype "bidirectional+no_connect"))
    )
    (net (code "90") (name "unconnected-(U2B-PE3-Pad2)") (class "Default")
      (node (ref "U2") (pin "2") (pinfunction "PE3_2") (pintype "bidirectional+no_connect"))
    )
    (net (code "91") (name "unconnected-(U2B-PE4-Pad3)") (class "Default")
      (node (ref "U2") (pin "3") (pinfunction "PE4_3") (pintype "bidirectional+no_connect"))
    )
    (net (code "92") (name "unconnected-(U2B-PE5-Pad4)") (class "Default")
      (node (ref "U2") (pin "4") (pinfunction "PE5_4") (pintype "bidirectional+no_connect"))
    )
    (net (code "93") (name "unconnected-(U2B-PE6-Pad5)") (class "Default")
      (node (ref "U2") (pin "5") (pinfunction "PE6_5") (pintype "bidirectional+no_connect"))
    )
    (net (code "94") (name "unconnected-(U2B-PE7-Pad37)") (class "Default")
      (node (ref "U2") (pin "37") (pinfunction "PE7_37") (pintype "bidirectional+no_connect"))
    )
    (net (code "95") (name "unconnected-(U2B-PE12-Pad42)") (class "Default")
      (node (ref "U2") (pin "42") (pinfunction "PE12_42") (pintype "bidirectional+no_connect"))
    )
    (net (code "96") (name "unconnected-(U5-DRDY-Pad8)") (class "Default")
      (node (ref "U5") (pin "8") (pinfunction "DRDY_8") (pintype "input+no_connect"))
    )
    (net (code "97") (name "unconnected-(U5-SD0{slash}SA1-Pad9)") (class "Default")
      (node (ref "U5") (pin "9") (pinfunction "SD0/SA1_9") (pintype "bidirectional"))
    )
    (net (code "98") (name "unconnected-(U6B-RESV-Pad7)") (class "Default")
      (node (ref "U6") (pin "7") (pinfunction "RESV_7") (pintype "passive"))
    )
  )
)
